# AD75019_breakout.net
KiCad netlist of a schematic drawn in EAGLE
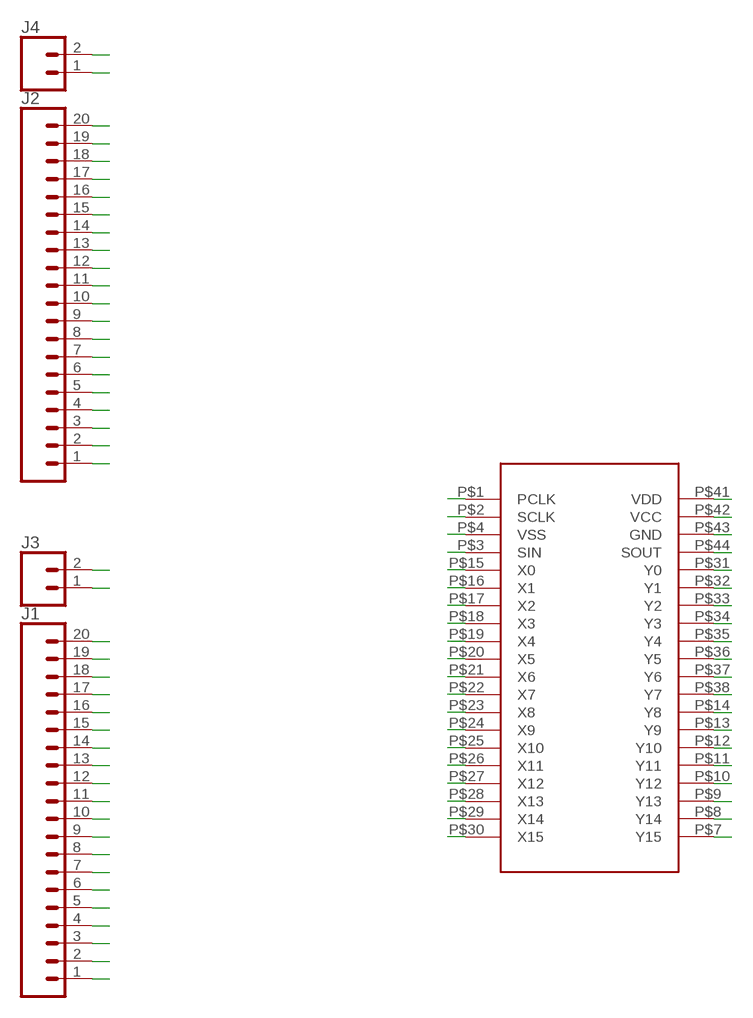
[diagram p0: schematic, sheet 1]

(export (version "E")
  (design (tool "Eeschema 10.0.6"))
  (components
    (comp (ref "J1")
      (value "CONN_20")
      (footprint "eagle-import:1X20")
      (libsource (lib "eagle-import") (part "CONN_20"))
    )
    (comp (ref "J2")
      (value "CONN_20")
      (footprint "eagle-import:1X20")
      (libsource (lib "eagle-import") (part "CONN_20"))
    )
    (comp (ref "J3")
      (value "CONN_02")
      (footprint "eagle-import:1X02")
      (libsource (lib "eagle-import") (part "CONN_02"))
    )
    (comp (ref "J4")
      (value "CONN_02")
      (footprint "eagle-import:1X02")
      (libsource (lib "eagle-import") (part "CONN_02"))
    )
    (comp (ref "U$1")
      (value "AD75019DIP44")
      (footprint "eagle-import:DIP44")
      (libsource (lib "eagle-import") (part "AD75019DIP44"))
    )
  )
  (nets
    (net (code "1") (name "/1") (class "Default")
      (node (ref "J1") (pin "1") (pinfunction "1_1") (pintype "passive"))
      (node (ref "U$1") (pin "P$1") (pinfunction "PCLK_P$1") (pintype "bidirectional"))
    )
    (net (code "2") (name "/2") (class "Default")
      (node (ref "J1") (pin "2") (pinfunction "2_2") (pintype "passive"))
      (node (ref "U$1") (pin "P$2") (pinfunction "SCLK_P$2") (pintype "bidirectional"))
    )
    (net (code "3") (name "/3") (class "Default")
      (node (ref "J1") (pin "3") (pinfunction "3_3") (pintype "passive"))
      (node (ref "U$1") (pin "P$3") (pinfunction "SIN_P$3") (pintype "bidirectional"))
    )
    (net (code "4") (name "/4") (class "Default")
      (node (ref "J1") (pin "4") (pinfunction "4_4") (pintype "passive"))
      (node (ref "U$1") (pin "P$4") (pinfunction "VSS_P$4") (pintype "bidirectional"))
    )
    (net (code "5") (name "/7") (class "Default")
      (node (ref "J1") (pin "7") (pinfunction "7_7") (pintype "passive"))
      (node (ref "U$1") (pin "P$7") (pinfunction "Y15_P$7") (pintype "bidirectional"))
    )
    (net (code "6") (name "/8") (class "Default")
      (node (ref "J1") (pin "8") (pinfunction "8_8") (pintype "passive"))
      (node (ref "U$1") (pin "P$8") (pinfunction "Y14_P$8") (pintype "bidirectional"))
    )
    (net (code "7") (name "/9") (class "Default")
      (node (ref "J1") (pin "9") (pinfunction "9_9") (pintype "passive"))
      (node (ref "U$1") (pin "P$9") (pinfunction "Y13_P$9") (pintype "bidirectional"))
    )
    (net (code "8") (name "/10") (class "Default")
      (node (ref "J1") (pin "10") (pinfunction "10_10") (pintype "passive"))
      (node (ref "U$1") (pin "P$10") (pinfunction "Y12_P$10") (pintype "bidirectional"))
    )
    (net (code "9") (name "/11") (class "Default")
      (node (ref "J1") (pin "11") (pinfunction "11_11") (pintype "passive"))
      (node (ref "U$1") (pin "P$11") (pinfunction "Y11_P$11") (pintype "bidirectional"))
    )
    (net (code "10") (name "/12") (class "Default")
      (node (ref "J1") (pin "12") (pinfunction "12_12") (pintype "passive"))
      (node (ref "U$1") (pin "P$12") (pinfunction "Y10_P$12") (pintype "bidirectional"))
    )
    (net (code "11") (name "/13") (class "Default")
      (node (ref "J1") (pin "13") (pinfunction "13_13") (pintype "passive"))
      (node (ref "U$1") (pin "P$13") (pinfunction "Y9_P$13") (pintype "bidirectional"))
    )
    (net (code "12") (name "/14") (class "Default")
      (node (ref "J1") (pin "14") (pinfunction "14_14") (pintype "passive"))
      (node (ref "U$1") (pin "P$14") (pinfunction "Y8_P$14") (pintype "bidirectional"))
    )
    (net (code "13") (name "/15") (class "Default")
      (node (ref "J1") (pin "15") (pinfunction "15_15") (pintype "passive"))
      (node (ref "U$1") (pin "P$15") (pinfunction "X0_P$15") (pintype "bidirectional"))
    )
    (net (code "14") (name "/16") (class "Default")
      (node (ref "J1") (pin "16") (pinfunction "16_16") (pintype "passive"))
      (node (ref "U$1") (pin "P$16") (pinfunction "X1_P$16") (pintype "bidirectional"))
    )
    (net (code "15") (name "/17") (class "Default")
      (node (ref "J1") (pin "17") (pinfunction "17_17") (pintype "passive"))
      (node (ref "U$1") (pin "P$17") (pinfunction "X2_P$17") (pintype "bidirectional"))
    )
    (net (code "16") (name "/18") (class "Default")
      (node (ref "J1") (pin "18") (pinfunction "18_18") (pintype "passive"))
      (node (ref "U$1") (pin "P$18") (pinfunction "X3_P$18") (pintype "bidirectional"))
    )
    (net (code "17") (name "/19") (class "Default")
      (node (ref "J1") (pin "19") (pinfunction "19_19") (pintype "passive"))
      (node (ref "U$1") (pin "P$19") (pinfunction "X4_P$19") (pintype "bidirectional"))
    )
    (net (code "18") (name "/20") (class "Default")
      (node (ref "J1") (pin "20") (pinfunction "20_20") (pintype "passive"))
      (node (ref "U$1") (pin "P$20") (pinfunction "X5_P$20") (pintype "bidirectional"))
    )
    (net (code "19") (name "/21") (class "Default")
      (node (ref "J3") (pin "1") (pinfunction "1_1") (pintype "passive"))
      (node (ref "U$1") (pin "P$21") (pinfunction "X6_P$21") (pintype "bidirectional"))
    )
    (net (code "20") (name "/22") (class "Default")
      (node (ref "J3") (pin "2") (pinfunction "2_2") (pintype "passive"))
      (node (ref "U$1") (pin "P$22") (pinfunction "X7_P$22") (pintype "bidirectional"))
    )
    (net (code "21") (name "/23") (class "Default")
      (node (ref "J2") (pin "1") (pinfunction "1_1") (pintype "passive"))
      (node (ref "U$1") (pin "P$23") (pinfunction "X8_P$23") (pintype "bidirectional"))
    )
    (net (code "22") (name "/24") (class "Default")
      (node (ref "J2") (pin "2") (pinfunction "2_2") (pintype "passive"))
      (node (ref "U$1") (pin "P$24") (pinfunction "X9_P$24") (pintype "bidirectional"))
    )
    (net (code "23") (name "/25") (class "Default")
      (node (ref "J2") (pin "3") (pinfunction "3_3") (pintype "passive"))
      (node (ref "U$1") (pin "P$25") (pinfunction "X10_P$25") (pintype "bidirectional"))
    )
    (net (code "24") (name "/26") (class "Default")
      (node (ref "J2") (pin "4") (pinfunction "4_4") (pintype "passive"))
      (node (ref "U$1") (pin "P$26") (pinfunction "X11_P$26") (pintype "bidirectional"))
    )
    (net (code "25") (name "/27") (class "Default")
      (node (ref "J2") (pin "5") (pinfunction "5_5") (pintype "passive"))
      (node (ref "U$1") (pin "P$27") (pinfunction "X12_P$27") (pintype "bidirectional"))
    )
    (net (code "26") (name "/28") (class "Default")
      (node (ref "J2") (pin "6") (pinfunction "6_6") (pintype "passive"))
      (node (ref "U$1") (pin "P$28") (pinfunction "X13_P$28") (pintype "bidirectional"))
    )
    (net (code "27") (name "/29") (class "Default")
      (node (ref "J2") (pin "7") (pinfunction "7_7") (pintype "passive"))
      (node (ref "U$1") (pin "P$29") (pinfunction "X14_P$29") (pintype "bidirectional"))
    )
    (net (code "28") (name "/30") (class "Default")
      (node (ref "J2") (pin "8") (pinfunction "8_8") (pintype "passive"))
      (node (ref "U$1") (pin "P$30") (pinfunction "X15_P$30") (pintype "bidirectional"))
    )
    (net (code "29") (name "/31") (class "Default")
      (node (ref "J2") (pin "9") (pinfunction "9_9") (pintype "passive"))
      (node (ref "U$1") (pin "P$31") (pinfunction "Y0_P$31") (pintype "bidirectional"))
    )
    (net (code "30") (name "/32") (class "Default")
      (node (ref "J2") (pin "10") (pinfunction "10_10") (pintype "passive"))
      (node (ref "U$1") (pin "P$32") (pinfunction "Y1_P$32") (pintype "bidirectional"))
    )
    (net (code "31") (name "/33") (class "Default")
      (node (ref "J2") (pin "11") (pinfunction "11_11") (pintype "passive"))
      (node (ref "U$1") (pin "P$33") (pinfunction "Y2_P$33") (pintype "bidirectional"))
    )
    (net (code "32") (name "/34") (class "Default")
      (node (ref "J2") (pin "12") (pinfunction "12_12") (pintype "passive"))
      (node (ref "U$1") (pin "P$34") (pinfunction "Y3_P$34") (pintype "bidirectional"))
    )
    (net (code "33") (name "/35") (class "Default")
      (node (ref "J2") (pin "13") (pinfunction "13_13") (pintype "passive"))
      (node (ref "U$1") (pin "P$35") (pinfunction "Y4_P$35") (pintype "bidirectional"))
    )
    (net (code "34") (name "/36") (class "Default")
      (node (ref "J2") (pin "14") (pinfunction "14_14") (pintype "passive"))
      (node (ref "U$1") (pin "P$36") (pinfunction "Y5_P$36") (pintype "bidirectional"))
    )
    (net (code "35") (name "/37") (class "Default")
      (node (ref "J2") (pin "15") (pinfunction "15_15") (pintype "passive"))
      (node (ref "U$1") (pin "P$37") (pinfunction "Y6_P$37") (pintype "bidirectional"))
    )
    (net (code "36") (name "/38") (class "Default")
      (node (ref "J2") (pin "16") (pinfunction "16_16") (pintype "passive"))
      (node (ref "U$1") (pin "P$38") (pinfunction "Y7_P$38") (pintype "bidirectional"))
    )
    (net (code "37") (name "/41") (class "Default")
      (node (ref "J2") (pin "19") (pinfunction "19_19") (pintype "passive"))
      (node (ref "U$1") (pin "P$41") (pinfunction "VDD_P$41") (pintype "bidirectional"))
    )
    (net (code "38") (name "/42") (class "Default")
      (node (ref "J2") (pin "20") (pinfunction "20_20") (pintype "passive"))
      (node (ref "U$1") (pin "P$42") (pinfunction "VCC_P$42") (pintype "bidirectional"))
    )
    (net (code "39") (name "/43") (class "Default")
      (node (ref "J4") (pin "1") (pinfunction "1_1") (pintype "passive"))
      (node (ref "U$1") (pin "P$43") (pinfunction "GND_P$43") (pintype "bidirectional"))
    )
    (net (code "40") (name "/44") (class "Default")
      (node (ref "J4") (pin "2") (pinfunction "2_2") (pintype "passive"))
      (node (ref "U$1") (pin "P$44") (pinfunction "SOUT_P$44") (pintype "bidirectional"))
    )
    (net (code "41") (name "unconnected-(J1-Pad5)") (class "Default")
      (node (ref "J1") (pin "5") (pinfunction "5_5") (pintype "passive"))
    )
    (net (code "42") (name "unconnected-(J1-Pad6)") (class "Default")
      (node (ref "J1") (pin "6") (pinfunction "6_6") (pintype "passive"))
    )
    (net (code "43") (name "unconnected-(J2-Pad17)") (class "Default")
      (node (ref "J2") (pin "17") (pinfunction "17_17") (pintype "passive"))
    )
    (net (code "44") (name "unconnected-(J2-Pad18)") (class "Default")
      (node (ref "J2") (pin "18") (pinfunction "18_18") (pintype "passive"))
    )
  )
)
